# Accerelometer.net
KiCad netlist of a schematic drawn in Altium Designer
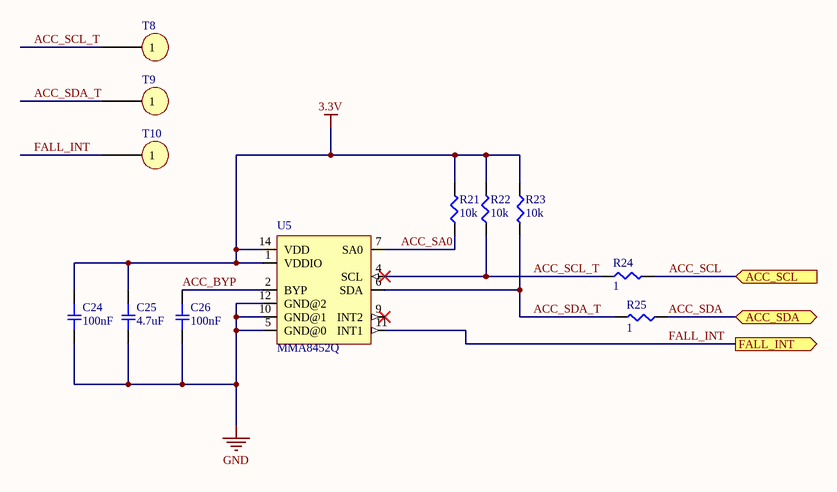
[diagram p0: Accerelometer.SchDoc]

(export (version "E")
  (design (tool "Eeschema 10.0.6"))
  (components
    (comp (ref "C24")
      (value "100nF")
      (footprint "0603-CAP")
      (fields (field (name "Comment") "0603C 100NF"))
      (libsource (lib "passive components") (part "0603C 100NF"))
    )
    (comp (ref "C25")
      (value "4.7uF")
      (footprint "0603-CAP")
      (fields (field (name "Comment") "0603C 4U7F"))
      (libsource (lib "passive components") (part "0603C 4U7F"))
    )
    (comp (ref "C26")
      (value "100nF")
      (footprint "0603-CAP")
      (fields (field (name "Comment") "0603C 100NF"))
      (libsource (lib "passive components") (part "0603C 100NF"))
    )
    (comp (ref "R21")
      (value "10k")
      (footprint "0603-RES")
      (fields (field (name "Comment") "0603R 10KR"))
      (libsource (lib "passive components") (part "0603R 10KR"))
    )
    (comp (ref "R22")
      (value "10k")
      (footprint "0603-RES")
      (fields (field (name "Comment") "0603R 10KR"))
      (libsource (lib "passive components") (part "0603R 10KR"))
    )
    (comp (ref "R23")
      (value "10k")
      (footprint "0603-RES")
      (fields (field (name "Comment") "0603R 10KR"))
      (libsource (lib "passive components") (part "0603R 10KR"))
    )
    (comp (ref "R24")
      (value "1")
      (footprint "0603-RES")
      (fields (field (name "Comment") "0603R 1R"))
      (libsource (lib "passive components") (part "0603R 1R"))
    )
    (comp (ref "R25")
      (value "1")
      (footprint "0603-RES")
      (fields (field (name "Comment") "0603R 1R"))
      (libsource (lib "passive components") (part "0603R 1R"))
    )
    (comp (ref "T8")
      (value "1pin_test")
      (footprint "1_PIN_test")
      (libsource (lib "2.54_Connectors") (part "1pin_test"))
    )
    (comp (ref "T9")
      (value "1pin_test")
      (footprint "1_PIN_test")
      (libsource (lib "2.54_Connectors") (part "1pin_test"))
    )
    (comp (ref "T10")
      (value "1pin_test")
      (footprint "1_PIN_test")
      (libsource (lib "2.54_Connectors") (part "1pin_test"))
    )
    (comp (ref "U5")
      (value "MMA8452Q")
      (footprint "*QFN-16_0.5MM")
      (description "Accelerometer X, Y, Z Axis , 2g, 4g, 8g 0.78Hz ~ 400Hz 16-QFN _3x3_")
      (fields (field (name "MP") "MMA8452QR1") (field (name "MF") "NXP Semiconductors"))
      (libsource (lib "MMA8452Q") (part "MMA8452Q"))
    )
  )
  (nets
    (net (code "1") (name "/ACC_BYP") (class "Default")
      (node (ref "C26") (pin "1") (pinfunction "1_1") (pintype "passive"))
      (node (ref "U5") (pin "2") (pinfunction "BYP_2") (pintype "passive"))
    )
    (net (code "2") (name "/ACC_SA0") (class "Default")
      (node (ref "R21") (pin "1") (pinfunction "1_1") (pintype "passive"))
      (node (ref "U5") (pin "7") (pinfunction "SA0_7") (pintype "passive"))
    )
    (net (code "3") (name "/ACC_SCL") (class "Default")
      (node (ref "R24") (pin "2") (pinfunction "2_2") (pintype "passive"))
    )
    (net (code "4") (name "/ACC_SCL_T") (class "Default")
      (node (ref "R22") (pin "1") (pinfunction "1_1") (pintype "passive"))
      (node (ref "R24") (pin "1") (pinfunction "1_1") (pintype "passive"))
      (node (ref "T8") (pin "1") (pinfunction "1_1") (pintype "passive"))
      (node (ref "U5") (pin "4") (pinfunction "SCL_4") (pintype "input"))
    )
    (net (code "5") (name "/ACC_SDA") (class "Default")
      (node (ref "R25") (pin "1") (pinfunction "1_1") (pintype "passive"))
    )
    (net (code "6") (name "/ACC_SDA_T") (class "Default")
      (node (ref "R23") (pin "2") (pinfunction "2_2") (pintype "passive"))
      (node (ref "R25") (pin "2") (pinfunction "2_2") (pintype "passive"))
      (node (ref "T9") (pin "1") (pinfunction "1_1") (pintype "passive"))
      (node (ref "U5") (pin "6") (pinfunction "SDA_6") (pintype "bidirectional"))
    )
    (net (code "7") (name "/FALL_INT") (class "Default")
      (node (ref "T10") (pin "1") (pinfunction "1_1") (pintype "passive"))
      (node (ref "U5") (pin "11") (pinfunction "INT1_11") (pintype "output"))
    )
    (net (code "8") (name "3.3V") (class "Default")
      (node (ref "C24") (pin "1") (pinfunction "1_1") (pintype "passive"))
      (node (ref "C25") (pin "1") (pinfunction "1_1") (pintype "passive"))
      (node (ref "R21") (pin "2") (pinfunction "2_2") (pintype "passive"))
      (node (ref "R22") (pin "2") (pinfunction "2_2") (pintype "passive"))
      (node (ref "R23") (pin "1") (pinfunction "1_1") (pintype "passive"))
      (node (ref "U5") (pin "1") (pinfunction "VDDIO_1") (pintype "power_in"))
      (node (ref "U5") (pin "14") (pinfunction "VDD_14") (pintype "power_in"))
    )
    (net (code "9") (name "GND") (class "Default")
      (node (ref "C24") (pin "2") (pinfunction "2_2") (pintype "passive"))
      (node (ref "C25") (pin "2") (pinfunction "2_2") (pintype "passive"))
      (node (ref "C26") (pin "2") (pinfunction "2_2") (pintype "passive"))
      (node (ref "U5") (pin "10") (pinfunction "GND@1_10") (pintype "passive"))
      (node (ref "U5") (pin "12") (pinfunction "GND@2_12") (pintype "passive"))
      (node (ref "U5") (pin "5") (pinfunction "GND@0_5") (pintype "passive"))
    )
    (net (code "10") (name "unconnected-(U5-INT2-Pad9)") (class "Default")
      (node (ref "U5") (pin "9") (pinfunction "INT2_9") (pintype "output+no_connect"))
    )
  )
)
